# design.net
KiCad netlist of a schematic drawn in EAGLE
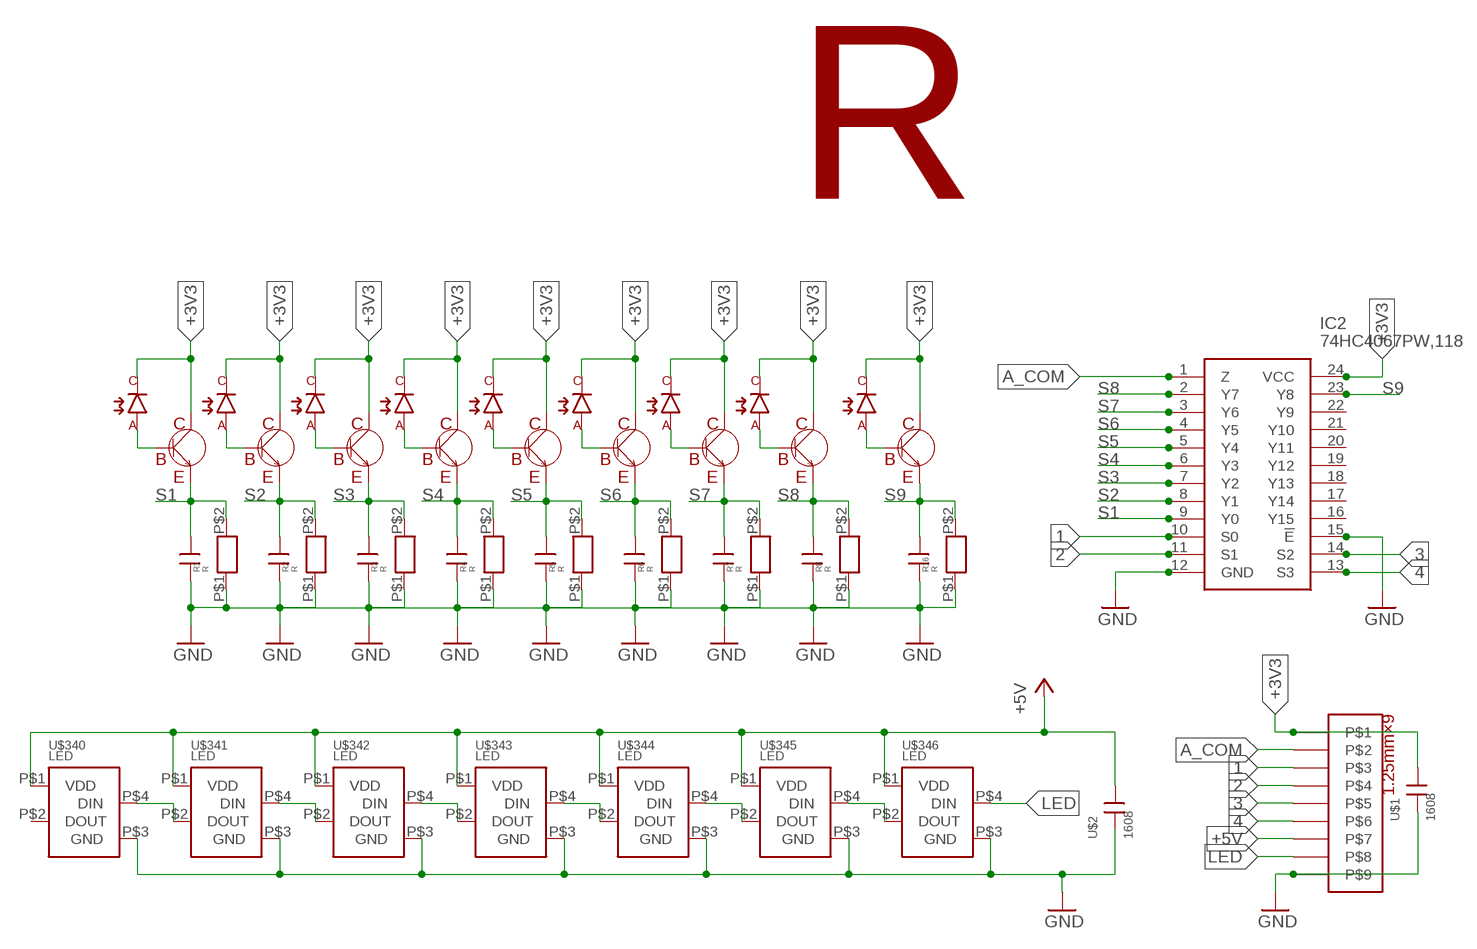
[diagram p0: schematic, sheet 1]

(export (version "E")
  (design (tool "Eeschema 10.0.6"))
  (components
    (comp (ref "C1")
      (value "1608")
      (footprint "eagle-import:CON")
      (libsource (lib "eagle-import") (part "1608"))
    )
    (comp (ref "C2")
      (value "1608")
      (footprint "eagle-import:CON")
      (libsource (lib "eagle-import") (part "1608"))
    )
    (comp (ref "C3")
      (value "1608")
      (footprint "eagle-import:CON")
      (libsource (lib "eagle-import") (part "1608"))
    )
    (comp (ref "C4")
      (value "1608")
      (footprint "eagle-import:CON")
      (libsource (lib "eagle-import") (part "1608"))
    )
    (comp (ref "C5")
      (value "1608")
      (footprint "eagle-import:CON")
      (libsource (lib "eagle-import") (part "1608"))
    )
    (comp (ref "C6")
      (value "1608")
      (footprint "eagle-import:CON")
      (libsource (lib "eagle-import") (part "1608"))
    )
    (comp (ref "C7")
      (value "1608")
      (footprint "eagle-import:CON")
      (libsource (lib "eagle-import") (part "1608"))
    )
    (comp (ref "C8")
      (value "1608")
      (footprint "eagle-import:CON")
      (libsource (lib "eagle-import") (part "1608"))
    )
    (comp (ref "C16")
      (value "1608")
      (footprint "eagle-import:CON")
      (libsource (lib "eagle-import") (part "1608"))
    )
    (comp (ref "IC2")
      (value "74HC4067PW,118")
      (footprint "eagle-import:SOP65P640X110-24N")
      (fields (field (name "MOUSER_PART_NUMBER") "771-74HC4067PW-T"))
      (libsource (lib "eagle-import") (part "74HC4067PW,118"))
    )
    (comp (ref "R1") (value "R") (footprint "eagle-import:1608") (libsource (lib "eagle-import") (part "R")))
    (comp (ref "R2") (value "R") (footprint "eagle-import:1608") (libsource (lib "eagle-import") (part "R")))
    (comp (ref "R3") (value "R") (footprint "eagle-import:1608") (libsource (lib "eagle-import") (part "R")))
    (comp (ref "R4") (value "R") (footprint "eagle-import:1608") (libsource (lib "eagle-import") (part "R")))
    (comp (ref "R5") (value "R") (footprint "eagle-import:1608") (libsource (lib "eagle-import") (part "R")))
    (comp (ref "R6") (value "R") (footprint "eagle-import:1608") (libsource (lib "eagle-import") (part "R")))
    (comp (ref "R7") (value "R") (footprint "eagle-import:1608") (libsource (lib "eagle-import") (part "R")))
    (comp (ref "R8") (value "R") (footprint "eagle-import:1608") (libsource (lib "eagle-import") (part "R")))
    (comp (ref "R16") (value "R") (footprint "eagle-import:1608") (libsource (lib "eagle-import") (part "R")))
    (comp (ref "U$1")
      (value "1608")
      (footprint "eagle-import:CON")
      (libsource (lib "eagle-import") (part "1608"))
    )
    (comp (ref "U$2")
      (value "1608")
      (footprint "eagle-import:CON")
      (libsource (lib "eagle-import") (part "1608"))
    )
    (comp (ref "U$3")
      (value "2CS2712")
      (footprint "eagle-import:TRANS_SSM3J325F,LF")
      (libsource (lib "eagle-import") (part "2CS2712"))
    )
    (comp (ref "U$4")
      (value "1MMCON")
      (footprint "eagle-import:1MMCON")
      (libsource (lib "eagle-import") (part "1MMCON"))
    )
    (comp (ref "U$5")
      (value "フォトダイオード")
      (footprint "eagle-import:フォトダイオード")
      (libsource (lib "eagle-import") (part "フォトダイオード"))
    )
    (comp (ref "U$6")
      (value "2CS2712")
      (footprint "eagle-import:TRANS_SSM3J325F,LF")
      (libsource (lib "eagle-import") (part "2CS2712"))
    )
    (comp (ref "U$7")
      (value "フォトダイオード")
      (footprint "eagle-import:フォトダイオード")
      (libsource (lib "eagle-import") (part "フォトダイオード"))
    )
    (comp (ref "U$8")
      (value "2CS2712")
      (footprint "eagle-import:TRANS_SSM3J325F,LF")
      (libsource (lib "eagle-import") (part "2CS2712"))
    )
    (comp (ref "U$9")
      (value "フォトダイオード")
      (footprint "eagle-import:フォトダイオード")
      (libsource (lib "eagle-import") (part "フォトダイオード"))
    )
    (comp (ref "U$10")
      (value "2CS2712")
      (footprint "eagle-import:TRANS_SSM3J325F,LF")
      (libsource (lib "eagle-import") (part "2CS2712"))
    )
    (comp (ref "U$11")
      (value "フォトダイオード")
      (footprint "eagle-import:フォトダイオード")
      (libsource (lib "eagle-import") (part "フォトダイオード"))
    )
    (comp (ref "U$12")
      (value "2CS2712")
      (footprint "eagle-import:TRANS_SSM3J325F,LF")
      (libsource (lib "eagle-import") (part "2CS2712"))
    )
    (comp (ref "U$13")
      (value "フォトダイオード")
      (footprint "eagle-import:フォトダイオード")
      (libsource (lib "eagle-import") (part "フォトダイオード"))
    )
    (comp (ref "U$14")
      (value "2CS2712")
      (footprint "eagle-import:TRANS_SSM3J325F,LF")
      (libsource (lib "eagle-import") (part "2CS2712"))
    )
    (comp (ref "U$15")
      (value "フォトダイオード")
      (footprint "eagle-import:フォトダイオード")
      (libsource (lib "eagle-import") (part "フォトダイオード"))
    )
    (comp (ref "U$16")
      (value "2CS2712")
      (footprint "eagle-import:TRANS_SSM3J325F,LF")
      (libsource (lib "eagle-import") (part "2CS2712"))
    )
    (comp (ref "U$17")
      (value "フォトダイオード")
      (footprint "eagle-import:フォトダイオード")
      (libsource (lib "eagle-import") (part "フォトダイオード"))
    )
    (comp (ref "U$18")
      (value "2CS2712")
      (footprint "eagle-import:TRANS_SSM3J325F,LF")
      (libsource (lib "eagle-import") (part "2CS2712"))
    )
    (comp (ref "U$19")
      (value "フォトダイオード")
      (footprint "eagle-import:フォトダイオード")
      (libsource (lib "eagle-import") (part "フォトダイオード"))
    )
    (comp (ref "U$20")
      (value "2CS2712")
      (footprint "eagle-import:TRANS_SSM3J325F,LF")
      (libsource (lib "eagle-import") (part "2CS2712"))
    )
    (comp (ref "U$21")
      (value "フォトダイオード")
      (footprint "eagle-import:フォトダイオード")
      (libsource (lib "eagle-import") (part "フォトダイオード"))
    )
    (comp (ref "U$340")
      (value "LED")
      (footprint "eagle-import:LED")
      (libsource (lib "eagle-import") (part "LED"))
    )
    (comp (ref "U$341")
      (value "LED")
      (footprint "eagle-import:LED")
      (libsource (lib "eagle-import") (part "LED"))
    )
    (comp (ref "U$342")
      (value "LED")
      (footprint "eagle-import:LED")
      (libsource (lib "eagle-import") (part "LED"))
    )
    (comp (ref "U$343")
      (value "LED")
      (footprint "eagle-import:LED")
      (libsource (lib "eagle-import") (part "LED"))
    )
    (comp (ref "U$344")
      (value "LED")
      (footprint "eagle-import:LED")
      (libsource (lib "eagle-import") (part "LED"))
    )
    (comp (ref "U$345")
      (value "LED")
      (footprint "eagle-import:LED")
      (libsource (lib "eagle-import") (part "LED"))
    )
    (comp (ref "U$346")
      (value "LED")
      (footprint "eagle-import:LED")
      (libsource (lib "eagle-import") (part "LED"))
    )
  )
  (nets
    (net (code "1") (name "+3V3") (class "Default")
      (node (ref "IC2") (pin "24") (pinfunction "VCC_24") (pintype "bidirectional"))
      (node (ref "U$1") (pin "P$1") (pinfunction "1_P$1") (pintype "bidirectional"))
      (node (ref "U$10") (pin "C") (pinfunction "C_C") (pintype "bidirectional"))
      (node (ref "U$11") (pin "C") (pinfunction "C_C") (pintype "bidirectional"))
      (node (ref "U$12") (pin "C") (pinfunction "C_C") (pintype "bidirectional"))
      (node (ref "U$13") (pin "C") (pinfunction "C_C") (pintype "bidirectional"))
      (node (ref "U$14") (pin "C") (pinfunction "C_C") (pintype "bidirectional"))
      (node (ref "U$15") (pin "C") (pinfunction "C_C") (pintype "bidirectional"))
      (node (ref "U$16") (pin "C") (pinfunction "C_C") (pintype "bidirectional"))
      (node (ref "U$17") (pin "C") (pinfunction "C_C") (pintype "bidirectional"))
      (node (ref "U$18") (pin "C") (pinfunction "C_C") (pintype "bidirectional"))
      (node (ref "U$19") (pin "C") (pinfunction "C_C") (pintype "bidirectional"))
      (node (ref "U$20") (pin "C") (pinfunction "C_C") (pintype "bidirectional"))
      (node (ref "U$21") (pin "C") (pinfunction "C_C") (pintype "bidirectional"))
      (node (ref "U$3") (pin "C") (pinfunction "C_C") (pintype "bidirectional"))
      (node (ref "U$4") (pin "P$1") (pinfunction "P$1_P$1") (pintype "bidirectional"))
      (node (ref "U$5") (pin "C") (pinfunction "C_C") (pintype "bidirectional"))
      (node (ref "U$6") (pin "C") (pinfunction "C_C") (pintype "bidirectional"))
      (node (ref "U$7") (pin "C") (pinfunction "C_C") (pintype "bidirectional"))
      (node (ref "U$8") (pin "C") (pinfunction "C_C") (pintype "bidirectional"))
      (node (ref "U$9") (pin "C") (pinfunction "C_C") (pintype "bidirectional"))
    )
    (net (code "2") (name "+5V") (class "Default")
      (node (ref "U$2") (pin "P$1") (pinfunction "1_P$1") (pintype "bidirectional"))
      (node (ref "U$340") (pin "P$1") (pinfunction "VDD_P$1") (pintype "bidirectional"))
      (node (ref "U$341") (pin "P$1") (pinfunction "VDD_P$1") (pintype "bidirectional"))
      (node (ref "U$342") (pin "P$1") (pinfunction "VDD_P$1") (pintype "bidirectional"))
      (node (ref "U$343") (pin "P$1") (pinfunction "VDD_P$1") (pintype "bidirectional"))
      (node (ref "U$344") (pin "P$1") (pinfunction "VDD_P$1") (pintype "bidirectional"))
      (node (ref "U$345") (pin "P$1") (pinfunction "VDD_P$1") (pintype "bidirectional"))
      (node (ref "U$346") (pin "P$1") (pinfunction "VDD_P$1") (pintype "bidirectional"))
      (node (ref "U$4") (pin "P$7") (pinfunction "P$7_P$7") (pintype "bidirectional"))
    )
    (net (code "3") (name "/S1") (class "Default")
      (node (ref "C1") (pin "P$1") (pinfunction "1_P$1") (pintype "bidirectional"))
      (node (ref "IC2") (pin "9") (pinfunction "Y0_9") (pintype "bidirectional"))
      (node (ref "R1") (pin "P$2") (pinfunction "P$2_P$2") (pintype "bidirectional"))
      (node (ref "U$3") (pin "E") (pinfunction "E_E") (pintype "bidirectional"))
    )
    (net (code "4") (name "/S2") (class "Default")
      (node (ref "C2") (pin "P$1") (pinfunction "1_P$1") (pintype "bidirectional"))
      (node (ref "IC2") (pin "8") (pinfunction "Y1_8") (pintype "bidirectional"))
      (node (ref "R2") (pin "P$2") (pinfunction "P$2_P$2") (pintype "bidirectional"))
      (node (ref "U$6") (pin "E") (pinfunction "E_E") (pintype "bidirectional"))
    )
    (net (code "5") (name "/S3") (class "Default")
      (node (ref "C3") (pin "P$1") (pinfunction "1_P$1") (pintype "bidirectional"))
      (node (ref "IC2") (pin "7") (pinfunction "Y2_7") (pintype "bidirectional"))
      (node (ref "R3") (pin "P$2") (pinfunction "P$2_P$2") (pintype "bidirectional"))
      (node (ref "U$8") (pin "E") (pinfunction "E_E") (pintype "bidirectional"))
    )
    (net (code "6") (name "/S4") (class "Default")
      (node (ref "C4") (pin "P$1") (pinfunction "1_P$1") (pintype "bidirectional"))
      (node (ref "IC2") (pin "6") (pinfunction "Y3_6") (pintype "bidirectional"))
      (node (ref "R4") (pin "P$2") (pinfunction "P$2_P$2") (pintype "bidirectional"))
      (node (ref "U$10") (pin "E") (pinfunction "E_E") (pintype "bidirectional"))
    )
    (net (code "7") (name "/S5") (class "Default")
      (node (ref "C5") (pin "P$1") (pinfunction "1_P$1") (pintype "bidirectional"))
      (node (ref "IC2") (pin "5") (pinfunction "Y4_5") (pintype "bidirectional"))
      (node (ref "R5") (pin "P$2") (pinfunction "P$2_P$2") (pintype "bidirectional"))
      (node (ref "U$12") (pin "E") (pinfunction "E_E") (pintype "bidirectional"))
    )
    (net (code "8") (name "/S6") (class "Default")
      (node (ref "C6") (pin "P$1") (pinfunction "1_P$1") (pintype "bidirectional"))
      (node (ref "IC2") (pin "4") (pinfunction "Y5_4") (pintype "bidirectional"))
      (node (ref "R6") (pin "P$2") (pinfunction "P$2_P$2") (pintype "bidirectional"))
      (node (ref "U$14") (pin "E") (pinfunction "E_E") (pintype "bidirectional"))
    )
    (net (code "9") (name "/S7") (class "Default")
      (node (ref "C7") (pin "P$1") (pinfunction "1_P$1") (pintype "bidirectional"))
      (node (ref "IC2") (pin "3") (pinfunction "Y6_3") (pintype "bidirectional"))
      (node (ref "R7") (pin "P$2") (pinfunction "P$2_P$2") (pintype "bidirectional"))
      (node (ref "U$16") (pin "E") (pinfunction "E_E") (pintype "bidirectional"))
    )
    (net (code "10") (name "/S8") (class "Default")
      (node (ref "C8") (pin "P$1") (pinfunction "1_P$1") (pintype "bidirectional"))
      (node (ref "IC2") (pin "2") (pinfunction "Y7_2") (pintype "bidirectional"))
      (node (ref "R8") (pin "P$2") (pinfunction "P$2_P$2") (pintype "bidirectional"))
      (node (ref "U$18") (pin "E") (pinfunction "E_E") (pintype "bidirectional"))
    )
    (net (code "11") (name "/S9") (class "Default")
      (node (ref "C16") (pin "P$1") (pinfunction "1_P$1") (pintype "bidirectional"))
      (node (ref "IC2") (pin "23") (pinfunction "Y8_23") (pintype "bidirectional"))
      (node (ref "R16") (pin "P$2") (pinfunction "P$2_P$2") (pintype "bidirectional"))
      (node (ref "U$20") (pin "E") (pinfunction "E_E") (pintype "bidirectional"))
    )
    (net (code "12") (name "1") (class "Default")
      (node (ref "IC2") (pin "10") (pinfunction "S0_10") (pintype "bidirectional"))
      (node (ref "U$4") (pin "P$3") (pinfunction "P$3_P$3") (pintype "bidirectional"))
    )
    (net (code "13") (name "2") (class "Default")
      (node (ref "IC2") (pin "11") (pinfunction "S1_11") (pintype "bidirectional"))
      (node (ref "U$4") (pin "P$4") (pinfunction "P$4_P$4") (pintype "bidirectional"))
    )
    (net (code "14") (name "3") (class "Default")
      (node (ref "IC2") (pin "14") (pinfunction "S2_14") (pintype "bidirectional"))
      (node (ref "U$4") (pin "P$5") (pinfunction "P$5_P$5") (pintype "bidirectional"))
    )
    (net (code "15") (name "4") (class "Default")
      (node (ref "IC2") (pin "13") (pinfunction "S3_13") (pintype "bidirectional"))
      (node (ref "U$4") (pin "P$6") (pinfunction "P$6_P$6") (pintype "bidirectional"))
    )
    (net (code "16") (name "A_COM") (class "Default")
      (node (ref "IC2") (pin "1") (pinfunction "Z_1") (pintype "bidirectional"))
      (node (ref "U$4") (pin "P$2") (pinfunction "P$2_P$2") (pintype "bidirectional"))
    )
    (net (code "17") (name "GND") (class "Default")
      (node (ref "C1") (pin "P$2") (pinfunction "2_P$2") (pintype "bidirectional"))
      (node (ref "C16") (pin "P$2") (pinfunction "2_P$2") (pintype "bidirectional"))
      (node (ref "C2") (pin "P$2") (pinfunction "2_P$2") (pintype "bidirectional"))
      (node (ref "C3") (pin "P$2") (pinfunction "2_P$2") (pintype "bidirectional"))
      (node (ref "C4") (pin "P$2") (pinfunction "2_P$2") (pintype "bidirectional"))
      (node (ref "C5") (pin "P$2") (pinfunction "2_P$2") (pintype "bidirectional"))
      (node (ref "C6") (pin "P$2") (pinfunction "2_P$2") (pintype "bidirectional"))
      (node (ref "C7") (pin "P$2") (pinfunction "2_P$2") (pintype "bidirectional"))
      (node (ref "C8") (pin "P$2") (pinfunction "2_P$2") (pintype "bidirectional"))
      (node (ref "IC2") (pin "12") (pinfunction "GND_12") (pintype "bidirectional"))
      (node (ref "IC2") (pin "15") (pinfunction "~{E}_15") (pintype "bidirectional"))
      (node (ref "R1") (pin "P$1") (pinfunction "P$1_P$1") (pintype "bidirectional"))
      (node (ref "R16") (pin "P$1") (pinfunction "P$1_P$1") (pintype "bidirectional"))
      (node (ref "R2") (pin "P$1") (pinfunction "P$1_P$1") (pintype "bidirectional"))
      (node (ref "R3") (pin "P$1") (pinfunction "P$1_P$1") (pintype "bidirectional"))
      (node (ref "R4") (pin "P$1") (pinfunction "P$1_P$1") (pintype "bidirectional"))
      (node (ref "R5") (pin "P$1") (pinfunction "P$1_P$1") (pintype "bidirectional"))
      (node (ref "R6") (pin "P$1") (pinfunction "P$1_P$1") (pintype "bidirectional"))
      (node (ref "R7") (pin "P$1") (pinfunction "P$1_P$1") (pintype "bidirectional"))
      (node (ref "R8") (pin "P$1") (pinfunction "P$1_P$1") (pintype "bidirectional"))
      (node (ref "U$1") (pin "P$2") (pinfunction "2_P$2") (pintype "bidirectional"))
      (node (ref "U$2") (pin "P$2") (pinfunction "2_P$2") (pintype "bidirectional"))
      (node (ref "U$340") (pin "P$3") (pinfunction "GND_P$3") (pintype "bidirectional"))
      (node (ref "U$341") (pin "P$3") (pinfunction "GND_P$3") (pintype "bidirectional"))
      (node (ref "U$342") (pin "P$3") (pinfunction "GND_P$3") (pintype "bidirectional"))
      (node (ref "U$343") (pin "P$3") (pinfunction "GND_P$3") (pintype "bidirectional"))
      (node (ref "U$344") (pin "P$3") (pinfunction "GND_P$3") (pintype "bidirectional"))
      (node (ref "U$345") (pin "P$3") (pinfunction "GND_P$3") (pintype "bidirectional"))
      (node (ref "U$346") (pin "P$3") (pinfunction "GND_P$3") (pintype "bidirectional"))
      (node (ref "U$4") (pin "P$9") (pinfunction "P$9_P$9") (pintype "bidirectional"))
    )
    (net (code "18") (name "LED") (class "Default")
      (node (ref "U$346") (pin "P$4") (pinfunction "DIN_P$4") (pintype "bidirectional"))
      (node (ref "U$4") (pin "P$8") (pinfunction "P$8_P$8") (pintype "bidirectional"))
    )
    (net (code "19") (name "Net-(U$3-PadB)") (class "Default")
      (node (ref "U$3") (pin "B") (pinfunction "B_B") (pintype "bidirectional"))
      (node (ref "U$5") (pin "A") (pinfunction "A_A") (pintype "bidirectional"))
    )
    (net (code "20") (name "Net-(U$6-PadB)") (class "Default")
      (node (ref "U$6") (pin "B") (pinfunction "B_B") (pintype "bidirectional"))
      (node (ref "U$7") (pin "A") (pinfunction "A_A") (pintype "bidirectional"))
    )
    (net (code "21") (name "Net-(U$8-PadB)") (class "Default")
      (node (ref "U$8") (pin "B") (pinfunction "B_B") (pintype "bidirectional"))
      (node (ref "U$9") (pin "A") (pinfunction "A_A") (pintype "bidirectional"))
    )
    (net (code "22") (name "Net-(U$10-PadB)") (class "Default")
      (node (ref "U$10") (pin "B") (pinfunction "B_B") (pintype "bidirectional"))
      (node (ref "U$11") (pin "A") (pinfunction "A_A") (pintype "bidirectional"))
    )
    (net (code "23") (name "Net-(U$12-PadB)") (class "Default")
      (node (ref "U$12") (pin "B") (pinfunction "B_B") (pintype "bidirectional"))
      (node (ref "U$13") (pin "A") (pinfunction "A_A") (pintype "bidirectional"))
    )
    (net (code "24") (name "Net-(U$14-PadB)") (class "Default")
      (node (ref "U$14") (pin "B") (pinfunction "B_B") (pintype "bidirectional"))
      (node (ref "U$15") (pin "A") (pinfunction "A_A") (pintype "bidirectional"))
    )
    (net (code "25") (name "Net-(U$16-PadB)") (class "Default")
      (node (ref "U$16") (pin "B") (pinfunction "B_B") (pintype "bidirectional"))
      (node (ref "U$17") (pin "A") (pinfunction "A_A") (pintype "bidirectional"))
    )
    (net (code "26") (name "Net-(U$18-PadB)") (class "Default")
      (node (ref "U$18") (pin "B") (pinfunction "B_B") (pintype "bidirectional"))
      (node (ref "U$19") (pin "A") (pinfunction "A_A") (pintype "bidirectional"))
    )
    (net (code "27") (name "Net-(U$20-PadB)") (class "Default")
      (node (ref "U$20") (pin "B") (pinfunction "B_B") (pintype "bidirectional"))
      (node (ref "U$21") (pin "A") (pinfunction "A_A") (pintype "bidirectional"))
    )
    (net (code "28") (name "Net-(U$340-DIN)") (class "Default")
      (node (ref "U$340") (pin "P$4") (pinfunction "DIN_P$4") (pintype "bidirectional"))
      (node (ref "U$341") (pin "P$2") (pinfunction "DOUT_P$2") (pintype "bidirectional"))
    )
    (net (code "29") (name "Net-(U$341-DIN)") (class "Default")
      (node (ref "U$341") (pin "P$4") (pinfunction "DIN_P$4") (pintype "bidirectional"))
      (node (ref "U$342") (pin "P$2") (pinfunction "DOUT_P$2") (pintype "bidirectional"))
    )
    (net (code "30") (name "Net-(U$342-DIN)") (class "Default")
      (node (ref "U$342") (pin "P$4") (pinfunction "DIN_P$4") (pintype "bidirectional"))
      (node (ref "U$343") (pin "P$2") (pinfunction "DOUT_P$2") (pintype "bidirectional"))
    )
    (net (code "31") (name "Net-(U$343-DIN)") (class "Default")
      (node (ref "U$343") (pin "P$4") (pinfunction "DIN_P$4") (pintype "bidirectional"))
      (node (ref "U$344") (pin "P$2") (pinfunction "DOUT_P$2") (pintype "bidirectional"))
    )
    (net (code "32") (name "Net-(U$344-DIN)") (class "Default")
      (node (ref "U$344") (pin "P$4") (pinfunction "DIN_P$4") (pintype "bidirectional"))
      (node (ref "U$345") (pin "P$2") (pinfunction "DOUT_P$2") (pintype "bidirectional"))
    )
    (net (code "33") (name "Net-(U$345-DIN)") (class "Default")
      (node (ref "U$345") (pin "P$4") (pinfunction "DIN_P$4") (pintype "bidirectional"))
      (node (ref "U$346") (pin "P$2") (pinfunction "DOUT_P$2") (pintype "bidirectional"))
    )
    (net (code "34") (name "unconnected-(IC2-Y9-Pad22)") (class "Default")
      (node (ref "IC2") (pin "22") (pinfunction "Y9_22") (pintype "bidirectional"))
    )
    (net (code "35") (name "unconnected-(IC2-Y10-Pad21)") (class "Default")
      (node (ref "IC2") (pin "21") (pinfunction "Y10_21") (pintype "bidirectional"))
    )
    (net (code "36") (name "unconnected-(IC2-Y11-Pad20)") (class "Default")
      (node (ref "IC2") (pin "20") (pinfunction "Y11_20") (pintype "bidirectional"))
    )
    (net (code "37") (name "unconnected-(IC2-Y12-Pad19)") (class "Default")
      (node (ref "IC2") (pin "19") (pinfunction "Y12_19") (pintype "bidirectional"))
    )
    (net (code "38") (name "unconnected-(IC2-Y13-Pad18)") (class "Default")
      (node (ref "IC2") (pin "18") (pinfunction "Y13_18") (pintype "bidirectional"))
    )
    (net (code "39") (name "unconnected-(IC2-Y14-Pad17)") (class "Default")
      (node (ref "IC2") (pin "17") (pinfunction "Y14_17") (pintype "bidirectional"))
    )
    (net (code "40") (name "unconnected-(IC2-Y15-Pad16)") (class "Default")
      (node (ref "IC2") (pin "16") (pinfunction "Y15_16") (pintype "bidirectional"))
    )
    (net (code "41") (name "unconnected-(U$340-DOUT-PadP$2)") (class "Default")
      (node (ref "U$340") (pin "P$2") (pinfunction "DOUT_P$2") (pintype "bidirectional"))
    )
  )
)
